# DigitalIO.net
KiCad netlist of a schematic drawn in Altium Designer
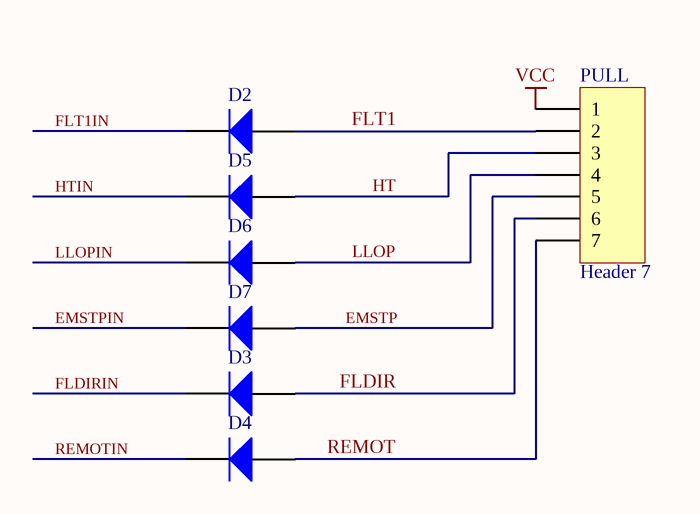
[diagram p0: DigitalIO.SchDoc]

(export (version "E")
  (design (tool "Eeschema 10.0.6"))
  (components
    (comp (ref "D2")
      (value "Diode 1N4001")
      (footprint "4148SMD")
      (description "1 Amp General Purpose Rectifier")
      (fields (field (name "PUBLISHER") "Altium Limited"))
      (libsource (lib "Miscellaneous Devices") (part "Diode 1N4001"))
    )
    (comp (ref "D3")
      (value "Diode 1N4001")
      (footprint "4148SMD")
      (description "1 Amp General Purpose Rectifier")
      (fields (field (name "PUBLISHER") "Altium Limited"))
      (libsource (lib "Miscellaneous Devices") (part "Diode 1N4001"))
    )
    (comp (ref "D4")
      (value "Diode 1N4001")
      (footprint "4148SMD")
      (description "1 Amp General Purpose Rectifier")
      (fields (field (name "PUBLISHER") "Altium Limited"))
      (libsource (lib "Miscellaneous Devices") (part "Diode 1N4001"))
    )
    (comp (ref "D5")
      (value "Diode 1N4001")
      (footprint "4148SMD")
      (description "1 Amp General Purpose Rectifier")
      (fields (field (name "PUBLISHER") "Altium Limited"))
      (libsource (lib "Miscellaneous Devices") (part "Diode 1N4001"))
    )
    (comp (ref "D6")
      (value "Diode 1N4001")
      (footprint "4148SMD")
      (description "1 Amp General Purpose Rectifier")
      (fields (field (name "PUBLISHER") "Altium Limited"))
      (libsource (lib "Miscellaneous Devices") (part "Diode 1N4001"))
    )
    (comp (ref "D7")
      (value "Diode 1N4001")
      (footprint "4148SMD")
      (description "1 Amp General Purpose Rectifier")
      (fields (field (name "PUBLISHER") "Altium Limited"))
      (libsource (lib "Miscellaneous Devices") (part "Diode 1N4001"))
    )
    (comp (ref "PULL")
      (value "Header 7")
      (footprint "HDR1X7")
      (description "Header, 7-Pin")
      (fields (field (name "PUBLISHER") "Altium Limited"))
      (libsource (lib "Miscellaneous Connectors") (part "Header 7"))
    )
  )
  (nets
    (net (code "1") (name "/EMSTP") (class "Default")
      (node (ref "D7") (pin "1") (pinfunction "A_1") (pintype "passive"))
      (node (ref "PULL") (pin "5") (pinfunction "5_5") (pintype "passive"))
    )
    (net (code "2") (name "/EMSTPIN") (class "Default")
      (node (ref "D7") (pin "2") (pinfunction "K_2") (pintype "passive"))
    )
    (net (code "3") (name "/FLDIR") (class "Default")
      (node (ref "D3") (pin "1") (pinfunction "A_1") (pintype "passive"))
      (node (ref "PULL") (pin "6") (pinfunction "6_6") (pintype "passive"))
    )
    (net (code "4") (name "/FLDIRIN") (class "Default")
      (node (ref "D3") (pin "2") (pinfunction "K_2") (pintype "passive"))
    )
    (net (code "5") (name "/FLT1") (class "Default")
      (node (ref "D2") (pin "1") (pinfunction "A_1") (pintype "passive"))
      (node (ref "PULL") (pin "2") (pinfunction "2_2") (pintype "passive"))
    )
    (net (code "6") (name "/FLT1IN") (class "Default")
      (node (ref "D2") (pin "2") (pinfunction "K_2") (pintype "passive"))
    )
    (net (code "7") (name "/HT") (class "Default")
      (node (ref "D5") (pin "1") (pinfunction "A_1") (pintype "passive"))
      (node (ref "PULL") (pin "3") (pinfunction "3_3") (pintype "passive"))
    )
    (net (code "8") (name "/HTIN") (class "Default")
      (node (ref "D5") (pin "2") (pinfunction "K_2") (pintype "passive"))
    )
    (net (code "9") (name "/LLOP") (class "Default")
      (node (ref "D6") (pin "1") (pinfunction "A_1") (pintype "passive"))
      (node (ref "PULL") (pin "4") (pinfunction "4_4") (pintype "passive"))
    )
    (net (code "10") (name "/LLOPIN") (class "Default")
      (node (ref "D6") (pin "2") (pinfunction "K_2") (pintype "passive"))
    )
    (net (code "11") (name "/REMOT") (class "Default")
      (node (ref "D4") (pin "1") (pinfunction "A_1") (pintype "passive"))
      (node (ref "PULL") (pin "7") (pinfunction "7_7") (pintype "passive"))
    )
    (net (code "12") (name "/REMOTIN") (class "Default")
      (node (ref "D4") (pin "2") (pinfunction "K_2") (pintype "passive"))
    )
    (net (code "13") (name "VCC") (class "Default")
      (node (ref "PULL") (pin "1") (pinfunction "1_1") (pintype "passive"))
    )
  )
)
